# GL3523.net
KiCad netlist of a schematic drawn in Altium Designer
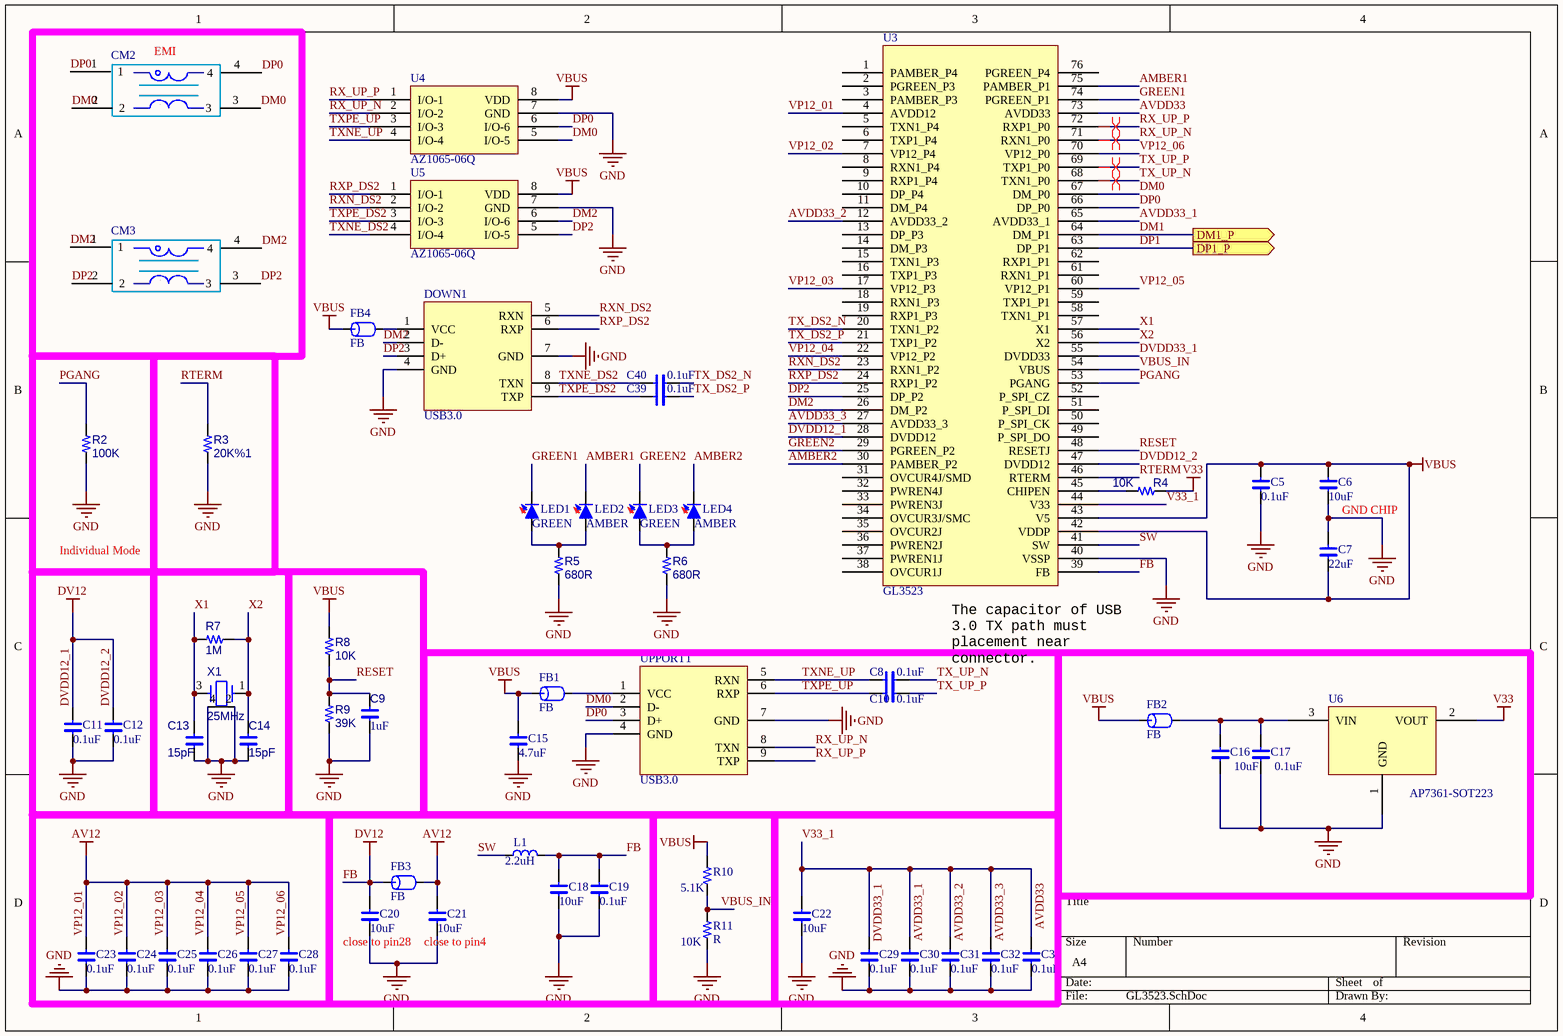
[diagram p0: GL3523.SchDoc]

(export (version "E")
  (design (tool "Eeschema 10.0.6"))
  (components
    (comp (ref "C5")
      (value "C")
      (footprint "0402CAPC1005X06N")
      (fields (field (name "ALTIUM_UNNAMED_1") "0.1uF"))
      (libsource (lib "Schlib_20130601") (part "C"))
    )
    (comp (ref "C6")
      (value "C")
      (footprint "0603CAPC1608X09N")
      (fields (field (name "ALTIUM_UNNAMED_1") "10uF"))
      (libsource (lib "Schlib_20130601") (part "C"))
    )
    (comp (ref "C7")
      (value "C")
      (footprint "0603CAPC1608X09N")
      (fields (field (name "ALTIUM_UNNAMED_1") "22uF"))
      (libsource (lib "Schlib_20130601") (part "C"))
    )
    (comp (ref "C8")
      (value "C")
      (footprint "0402CAPC1005X06N")
      (fields (field (name "ALTIUM_UNNAMED_1") "0.1uF"))
      (libsource (lib "Schlib_20130601") (part "C"))
    )
    (comp (ref "C9")
      (value "15pF")
      (footprint "0402CAPC1005X06N")
      (description "C")
      (fields (field (name "ALTIUM_UNNAMED_1") "1uF"))
      (libsource (lib "Schlib_20130101") (part "C"))
    )
    (comp (ref "C10")
      (value "C")
      (footprint "0402CAPC1005X06N")
      (fields (field (name "ALTIUM_UNNAMED_1") "0.1uF"))
      (libsource (lib "Schlib_20130601") (part "C"))
    )
    (comp (ref "C11")
      (value "C")
      (footprint "0402CAPC1005X06N")
      (fields (field (name "ALTIUM_UNNAMED_1") "0.1uF"))
      (libsource (lib "Schlib_20130601") (part "C"))
    )
    (comp (ref "C12")
      (value "C")
      (footprint "0402CAPC1005X06N")
      (fields (field (name "ALTIUM_UNNAMED_1") "0.1uF"))
      (libsource (lib "Schlib_20130601") (part "C"))
    )
    (comp (ref "C13")
      (value "15pF")
      (footprint "0402CAPC1005X06N")
      (description "C")
      (libsource (lib "Schlib_20130101") (part "C"))
    )
    (comp (ref "C14")
      (value "15pF")
      (footprint "0402CAPC1005X06N")
      (description "C")
      (libsource (lib "Schlib_20130101") (part "C"))
    )
    (comp (ref "C15")
      (value "C")
      (footprint "0603CAPC1608X09N")
      (fields (field (name "ALTIUM_UNNAMED_1") "4.7uF"))
      (libsource (lib "Schlib_20130601") (part "C"))
    )
    (comp (ref "C16")
      (value "C")
      (footprint "0603CAPC1608X09N")
      (fields (field (name "ALTIUM_UNNAMED_1") "10uF"))
      (libsource (lib "Schlib_20130601") (part "C"))
    )
    (comp (ref "C17")
      (value "C")
      (footprint "0402CAPC1005X06N")
      (fields (field (name "ALTIUM_UNNAMED_1") "0.1uF"))
      (libsource (lib "Schlib_20130601") (part "C"))
    )
    (comp (ref "C18")
      (value "C")
      (footprint "0603CAPC1608X09N")
      (fields (field (name "ALTIUM_UNNAMED_1") "10uF"))
      (libsource (lib "Schlib_20130601") (part "C"))
    )
    (comp (ref "C19")
      (value "C")
      (footprint "0402CAPC1005X06N")
      (fields (field (name "ALTIUM_UNNAMED_1") "0.1uF"))
      (libsource (lib "Schlib_20130601") (part "C"))
    )
    (comp (ref "C20")
      (value "C")
      (footprint "0603CAPC1608X09N")
      (fields (field (name "ALTIUM_UNNAMED_1") "10uF"))
      (libsource (lib "Schlib_20130601") (part "C"))
    )
    (comp (ref "C21")
      (value "C")
      (footprint "0603CAPC1608X09N")
      (fields (field (name "ALTIUM_UNNAMED_1") "10uF"))
      (libsource (lib "Schlib_20130601") (part "C"))
    )
    (comp (ref "C22")
      (value "C")
      (footprint "0603CAPC1608X09N")
      (fields (field (name "ALTIUM_UNNAMED_1") "10uF"))
      (libsource (lib "Schlib_20130601") (part "C"))
    )
    (comp (ref "C23")
      (value "C")
      (footprint "0402CAPC1005X06N")
      (fields (field (name "ALTIUM_UNNAMED_1") "0.1uF"))
      (libsource (lib "Schlib_20130601") (part "C"))
    )
    (comp (ref "C24")
      (value "C")
      (footprint "0402CAPC1005X06N")
      (fields (field (name "ALTIUM_UNNAMED_1") "0.1uF"))
      (libsource (lib "Schlib_20130601") (part "C"))
    )
    (comp (ref "C25")
      (value "C")
      (footprint "0402CAPC1005X06N")
      (fields (field (name "ALTIUM_UNNAMED_1") "0.1uF"))
      (libsource (lib "Schlib_20130601") (part "C"))
    )
    (comp (ref "C26")
      (value "C")
      (footprint "0402CAPC1005X06N")
      (fields (field (name "ALTIUM_UNNAMED_1") "0.1uF"))
      (libsource (lib "Schlib_20130601") (part "C"))
    )
    (comp (ref "C27")
      (value "C")
      (footprint "0402CAPC1005X06N")
      (fields (field (name "ALTIUM_UNNAMED_1") "0.1uF"))
      (libsource (lib "Schlib_20130601") (part "C"))
    )
    (comp (ref "C28")
      (value "C")
      (footprint "0402CAPC1005X06N")
      (fields (field (name "ALTIUM_UNNAMED_1") "0.1uF"))
      (libsource (lib "Schlib_20130601") (part "C"))
    )
    (comp (ref "C29")
      (value "C")
      (footprint "0402CAPC1005X06N")
      (fields (field (name "ALTIUM_UNNAMED_1") "0.1uF"))
      (libsource (lib "Schlib_20130601") (part "C"))
    )
    (comp (ref "C30")
      (value "C")
      (footprint "0402CAPC1005X06N")
      (fields (field (name "ALTIUM_UNNAMED_1") "0.1uF"))
      (libsource (lib "Schlib_20130601") (part "C"))
    )
    (comp (ref "C31")
      (value "C")
      (footprint "0402CAPC1005X06N")
      (fields (field (name "ALTIUM_UNNAMED_1") "0.1uF"))
      (libsource (lib "Schlib_20130601") (part "C"))
    )
    (comp (ref "C32")
      (value "C")
      (footprint "0402CAPC1005X06N")
      (fields (field (name "ALTIUM_UNNAMED_1") "0.1uF"))
      (libsource (lib "Schlib_20130601") (part "C"))
    )
    (comp (ref "C33")
      (value "C")
      (footprint "0402CAPC1005X06N")
      (fields (field (name "ALTIUM_UNNAMED_1") "0.1uF"))
      (libsource (lib "Schlib_20130601") (part "C"))
    )
    (comp (ref "C39")
      (value "C")
      (footprint "0402CAPC1005X06N")
      (fields (field (name "ALTIUM_UNNAMED_1") "0.1uF"))
      (libsource (lib "Schlib_20130601") (part "C"))
    )
    (comp (ref "C40")
      (value "C")
      (footprint "0402CAPC1005X06N")
      (fields (field (name "ALTIUM_UNNAMED_1") "0.1uF"))
      (libsource (lib "Schlib_20130601") (part "C"))
    )
    (comp (ref "CM2")
      (value "CM")
      (footprint "SMD_4P")
      (description "USB Comon Choke")
      (libsource (lib "Schlib_20130601") (part "CM"))
    )
    (comp (ref "CM3")
      (value "CM")
      (footprint "SMD_4P")
      (description "USB Comon Choke")
      (libsource (lib "Schlib_20130601") (part "CM"))
    )
    (comp (ref "DOWN1")
      (value "USB3.0")
      (footprint "USB3.0-A-Pin")
      (libsource (lib "Schlib_20130601") (part "USB3.0"))
    )
    (comp (ref "FB1") (value "FB") (footprint "0805FB") (libsource (lib "Schlib_20130601") (part "FB")))
    (comp (ref "FB2") (value "FB") (footprint "0805FB") (libsource (lib "Schlib_20130601") (part "FB")))
    (comp (ref "FB3") (value "FB") (footprint "0805FB") (libsource (lib "Schlib_20130601") (part "FB")))
    (comp (ref "FB4") (value "FB") (footprint "0805FB") (libsource (lib "Schlib_20130601") (part "FB")))
    (comp (ref "L1")
      (value "L")
      (footprint "0805FB")
      (fields (field (name "ALTIUM_UNNAMED_1") "2.2uH"))
      (libsource (lib "Schlib_20130601") (part "L"))
    )
    (comp (ref "LED1")
      (value "GREEN")
      (footprint "0603LEDC1608X04N")
      (description "Chip LED")
      (fields (field (name "PUBLISHER") "ChenTao"))
      (libsource (lib "THTF_SCHLIB_V1P0_20130724") (part "LED"))
    )
    (comp (ref "LED2")
      (value "AMBER")
      (footprint "0603LEDC1608X04N")
      (description "Chip LED")
      (fields (field (name "PUBLISHER") "ChenTao"))
      (libsource (lib "THTF_SCHLIB_V1P0_20130724") (part "LED"))
    )
    (comp (ref "LED3")
      (value "GREEN")
      (footprint "0603LEDC1608X04N")
      (description "Chip LED")
      (fields (field (name "PUBLISHER") "ChenTao"))
      (libsource (lib "THTF_SCHLIB_V1P0_20130724") (part "LED"))
    )
    (comp (ref "LED4")
      (value "AMBER")
      (footprint "0603LEDC1608X04N")
      (description "Chip LED")
      (fields (field (name "PUBLISHER") "ChenTao"))
      (libsource (lib "THTF_SCHLIB_V1P0_20130724") (part "LED"))
    )
    (comp (ref "R2")
      (value "100K")
      (footprint "0402RESC1005X04N")
      (description "R")
      (libsource (lib "Schlib_20130101") (part "R"))
    )
    (comp (ref "R3")
      (value "20K%1")
      (footprint "0402RESC1005X04N")
      (description "R")
      (libsource (lib "Schlib_20130101") (part "R"))
    )
    (comp (ref "R4")
      (value "10K")
      (footprint "0402RESC1005X04N")
      (description "R")
      (libsource (lib "Schlib_20130101") (part "R"))
    )
    (comp (ref "R5")
      (value "680R")
      (footprint "0402RESC1005X04N")
      (description "R")
      (libsource (lib "Schlib_20130101") (part "R"))
    )
    (comp (ref "R6")
      (value "680R")
      (footprint "0402RESC1005X04N")
      (description "R")
      (libsource (lib "Schlib_20130101") (part "R"))
    )
    (comp (ref "R7")
      (value "1M")
      (footprint "0402RESC1005X04N")
      (description "R")
      (libsource (lib "Schlib_20130101") (part "R"))
    )
    (comp (ref "R8")
      (value "10K")
      (footprint "0402RESC1005X04N")
      (description "R")
      (libsource (lib "Schlib_20130101") (part "R"))
    )
    (comp (ref "R9")
      (value "39K")
      (footprint "0402RESC1005X04N")
      (description "R")
      (libsource (lib "Schlib_20130101") (part "R"))
    )
    (comp (ref "R10")
      (value "R")
      (footprint "0603R")
      (fields (field (name "ALTIUM_UNNAMED_1") "5.1K"))
      (libsource (lib "Schlib_20130601") (part "R"))
    )
    (comp (ref "R11")
      (value "R")
      (footprint "0603R")
      (fields (field (name "ALTIUM_UNNAMED_1") "10K"))
      (libsource (lib "Schlib_20130601") (part "R"))
    )
    (comp (ref "U3")
      (value "GL3523")
      (footprint "QFN-76")
      (libsource (lib "Schlib_20130601") (part "GL3523"))
    )
    (comp (ref "U4")
      (value "AZ1065-06Q")
      (footprint "MSOP-8")
      (libsource (lib "Schlib_20130601") (part "AZ1065-06Q"))
    )
    (comp (ref "U5")
      (value "AZ1065-06Q")
      (footprint "MSOP-8")
      (libsource (lib "Schlib_20130601") (part "AZ1065-06Q"))
    )
    (comp (ref "U6")
      (value "AP7361-SOT223")
      (footprint "SOT230P700X180-4N")
      (libsource (lib "Schlib_20130601") (part "AMS1117-3.3"))
    )
    (comp (ref "UPPORT1")
      (value "USB3.0")
      (footprint "USB3.0-G")
      (libsource (lib "Schlib_20130601") (part "USB3.0"))
    )
    (comp (ref "X1")
      (value "25MHz")
      (footprint "CPX-32")
      (libsource (lib "Schlib_20110825") (part "CRYSTAL-4"))
    )
  )
  (nets
    (net (code "1") (name "/AMBER1") (class "Default")
      (node (ref "LED2") (pin "K") (pintype "passive"))
      (node (ref "U3") (pin "75") (pinfunction "PAMBER_P1_75") (pintype "passive"))
    )
    (net (code "2") (name "/AMBER2") (class "Default")
      (node (ref "LED4") (pin "K") (pintype "passive"))
      (node (ref "U3") (pin "30") (pinfunction "PAMBER_P2_30") (pintype "passive"))
    )
    (net (code "3") (name "/AVDD33") (class "Default")
      (node (ref "C22") (pin "2") (pintype "passive"))
      (node (ref "C29") (pin "2") (pintype "passive"))
      (node (ref "C30") (pin "2") (pintype "passive"))
      (node (ref "C31") (pin "2") (pintype "passive"))
      (node (ref "C32") (pin "2") (pintype "passive"))
      (node (ref "C33") (pin "2") (pintype "passive"))
      (node (ref "U3") (pin "12") (pinfunction "AVDD33_2_12") (pintype "passive"))
      (node (ref "U3") (pin "27") (pinfunction "AVDD33_3_27") (pintype "passive"))
      (node (ref "U3") (pin "44") (pinfunction "V33_44") (pintype "passive"))
      (node (ref "U3") (pin "55") (pinfunction "DVDD33_55") (pintype "passive"))
      (node (ref "U3") (pin "65") (pinfunction "AVDD33_1_65") (pintype "passive"))
      (node (ref "U3") (pin "73") (pinfunction "AVDD33_73") (pintype "passive"))
    )
    (net (code "4") (name "/DM0") (class "Default")
      (node (ref "CM2") (pin "2") (pinfunction "2_2") (pintype "passive"))
      (node (ref "CM2") (pin "3") (pinfunction "3_3") (pintype "passive"))
      (node (ref "U3") (pin "67") (pinfunction "DM_P0_67") (pintype "passive"))
      (node (ref "U4") (pin "5") (pinfunction "I/O-5_5") (pintype "passive"))
      (node (ref "UPPORT1") (pin "2") (pinfunction "D-_2") (pintype "passive"))
    )
    (net (code "5") (name "/DM1") (class "Default")
      (node (ref "U3") (pin "64") (pinfunction "DM_P1_64") (pintype "passive"))
    )
    (net (code "6") (name "/DM2") (class "Default")
      (node (ref "CM3") (pin "1") (pinfunction "1_1") (pintype "passive"))
      (node (ref "CM3") (pin "4") (pinfunction "4_4") (pintype "passive"))
      (node (ref "DOWN1") (pin "2") (pinfunction "D-_2") (pintype "passive"))
      (node (ref "U3") (pin "26") (pinfunction "DM_P2_26") (pintype "passive"))
      (node (ref "U5") (pin "6") (pinfunction "I/O-6_6") (pintype "passive"))
    )
    (net (code "7") (name "/DP0") (class "Default")
      (node (ref "CM2") (pin "1") (pinfunction "1_1") (pintype "passive"))
      (node (ref "CM2") (pin "4") (pinfunction "4_4") (pintype "passive"))
      (node (ref "U3") (pin "66") (pinfunction "DP_P0_66") (pintype "passive"))
      (node (ref "U4") (pin "6") (pinfunction "I/O-6_6") (pintype "passive"))
      (node (ref "UPPORT1") (pin "3") (pinfunction "D+_3") (pintype "passive"))
    )
    (net (code "8") (name "/DP1") (class "Default")
      (node (ref "U3") (pin "63") (pinfunction "DP_P1_63") (pintype "passive"))
    )
    (net (code "9") (name "/DP2") (class "Default")
      (node (ref "CM3") (pin "2") (pinfunction "2_2") (pintype "passive"))
      (node (ref "CM3") (pin "3") (pinfunction "3_3") (pintype "passive"))
      (node (ref "DOWN1") (pin "3") (pinfunction "D+_3") (pintype "passive"))
      (node (ref "U3") (pin "25") (pinfunction "DP_P2_25") (pintype "passive"))
      (node (ref "U5") (pin "5") (pinfunction "I/O-5_5") (pintype "passive"))
    )
    (net (code "10") (name "/GREEN1") (class "Default")
      (node (ref "LED1") (pin "K") (pintype "passive"))
      (node (ref "U3") (pin "74") (pinfunction "PGREEN_P1_74") (pintype "passive"))
    )
    (net (code "11") (name "/GREEN2") (class "Default")
      (node (ref "LED3") (pin "K") (pintype "passive"))
      (node (ref "U3") (pin "29") (pinfunction "PGREEN_P2_29") (pintype "passive"))
    )
    (net (code "12") (name "/PGANG") (class "Default")
      (node (ref "R2") (pin "1") (pintype "passive"))
      (node (ref "U3") (pin "53") (pinfunction "PGANG_53") (pintype "passive"))
    )
    (net (code "13") (name "/RESET") (class "Default")
      (node (ref "C9") (pin "1") (pintype "passive"))
      (node (ref "R8") (pin "2") (pintype "passive"))
      (node (ref "R9") (pin "1") (pintype "passive"))
      (node (ref "U3") (pin "48") (pinfunction "RESETJ_48") (pintype "passive"))
    )
    (net (code "14") (name "/RTERM") (class "Default")
      (node (ref "R3") (pin "1") (pintype "passive"))
      (node (ref "U3") (pin "46") (pinfunction "RTERM_46") (pintype "passive"))
    )
    (net (code "15") (name "/RXN_DS2") (class "Default")
      (node (ref "DOWN1") (pin "5") (pinfunction "RXN_5") (pintype "passive"))
      (node (ref "U3") (pin "23") (pinfunction "RXN1_P2_23") (pintype "passive"))
      (node (ref "U5") (pin "2") (pinfunction "I/O-2_2") (pintype "passive"))
    )
    (net (code "16") (name "/RXP_DS2") (class "Default")
      (node (ref "DOWN1") (pin "6") (pinfunction "RXP_6") (pintype "passive"))
      (node (ref "U3") (pin "24") (pinfunction "RXP1_P2_24") (pintype "passive"))
      (node (ref "U5") (pin "1") (pinfunction "I/O-1_1") (pintype "passive"))
    )
    (net (code "17") (name "/RX_UP_N") (class "Default")
      (node (ref "U3") (pin "71") (pinfunction "RXN1_P0_71") (pintype "passive"))
      (node (ref "U4") (pin "2") (pinfunction "I/O-2_2") (pintype "passive"))
      (node (ref "UPPORT1") (pin "8") (pinfunction "TXN_8") (pintype "passive"))
    )
    (net (code "18") (name "/RX_UP_P") (class "Default")
      (node (ref "U3") (pin "72") (pinfunction "RXP1_P0_72") (pintype "passive"))
      (node (ref "U4") (pin "1") (pinfunction "I/O-1_1") (pintype "passive"))
      (node (ref "UPPORT1") (pin "9") (pinfunction "TXP_9") (pintype "passive"))
    )
    (net (code "19") (name "/SW") (class "Default")
      (node (ref "L1") (pin "1") (pintype "passive"))
      (node (ref "U3") (pin "41") (pinfunction "SW_41") (pintype "passive"))
    )
    (net (code "20") (name "/TXNE_DS2") (class "Default")
      (node (ref "C40") (pin "2") (pintype "passive"))
      (node (ref "DOWN1") (pin "8") (pinfunction "TXN_8") (pintype "passive"))
      (node (ref "U5") (pin "4") (pinfunction "I/O-4_4") (pintype "passive"))
    )
    (net (code "21") (name "/TXNE_UP") (class "Default")
      (node (ref "C8") (pin "2") (pintype "passive"))
      (node (ref "U4") (pin "4") (pinfunction "I/O-4_4") (pintype "passive"))
      (node (ref "UPPORT1") (pin "5") (pinfunction "RXN_5") (pintype "passive"))
    )
    (net (code "22") (name "/TXPE_DS2") (class "Default")
      (node (ref "C39") (pin "2") (pintype "passive"))
      (node (ref "DOWN1") (pin "9") (pinfunction "TXP_9") (pintype "passive"))
      (node (ref "U5") (pin "3") (pinfunction "I/O-3_3") (pintype "passive"))
    )
    (net (code "23") (name "/TXPE_UP") (class "Default")
      (node (ref "C10") (pin "2") (pintype "passive"))
      (node (ref "U4") (pin "3") (pinfunction "I/O-3_3") (pintype "passive"))
      (node (ref "UPPORT1") (pin "6") (pinfunction "RXP_6") (pintype "passive"))
    )
    (net (code "24") (name "/TX_DS2_N") (class "Default")
      (node (ref "C40") (pin "1") (pintype "passive"))
      (node (ref "U3") (pin "20") (pinfunction "TXN1_P2_20") (pintype "passive"))
    )
    (net (code "25") (name "/TX_DS2_P") (class "Default")
      (node (ref "C39") (pin "1") (pintype "passive"))
      (node (ref "U3") (pin "21") (pinfunction "TXP1_P2_21") (pintype "passive"))
    )
    (net (code "26") (name "/TX_UP_N") (class "Default")
      (node (ref "C8") (pin "1") (pintype "passive"))
      (node (ref "U3") (pin "68") (pinfunction "TXN1_P0_68") (pintype "passive"))
    )
    (net (code "27") (name "/TX_UP_P") (class "Default")
      (node (ref "C10") (pin "1") (pintype "passive"))
      (node (ref "U3") (pin "69") (pinfunction "TXP1_P0_69") (pintype "passive"))
    )
    (net (code "28") (name "/VBUS_IN") (class "Default")
      (node (ref "R10") (pin "1") (pintype "passive"))
      (node (ref "R11") (pin "2") (pintype "passive"))
      (node (ref "U3") (pin "54") (pinfunction "VBUS_54") (pintype "passive"))
    )
    (net (code "29") (name "/X1") (class "Default")
      (node (ref "C13") (pin "2") (pintype "passive"))
      (node (ref "R7") (pin "2") (pintype "passive"))
      (node (ref "U3") (pin "57") (pinfunction "X1_57") (pintype "passive"))
      (node (ref "X1") (pin "3") (pinfunction "X2_3") (pintype "passive"))
    )
    (net (code "30") (name "/X2") (class "Default")
      (node (ref "C14") (pin "1") (pintype "passive"))
      (node (ref "R7") (pin "1") (pintype "passive"))
      (node (ref "U3") (pin "56") (pinfunction "X2_56") (pintype "passive"))
      (node (ref "X1") (pin "1") (pinfunction "X1_1") (pintype "passive"))
    )
    (net (code "31") (name "AV12") (class "Default")
      (node (ref "C21") (pin "2") (pintype "passive"))
      (node (ref "C23") (pin "2") (pintype "passive"))
      (node (ref "C24") (pin "2") (pintype "passive"))
      (node (ref "C25") (pin "2") (pintype "passive"))
      (node (ref "C26") (pin "2") (pintype "passive"))
      (node (ref "C27") (pin "2") (pintype "passive"))
      (node (ref "C28") (pin "2") (pintype "passive"))
      (node (ref "FB3") (pin "2") (pintype "passive"))
      (node (ref "U3") (pin "17") (pinfunction "VP12_P3_17") (pintype "passive"))
      (node (ref "U3") (pin "22") (pinfunction "VP12_P2_22") (pintype "passive"))
      (node (ref "U3") (pin "4") (pinfunction "AVDD12_4") (pintype "passive"))
      (node (ref "U3") (pin "60") (pinfunction "VP12_P1_60") (pintype "passive"))
      (node (ref "U3") (pin "7") (pinfunction "VP12_P4_7") (pintype "passive"))
      (node (ref "U3") (pin "70") (pinfunction "VP12_P0_70") (pintype "passive"))
    )
    (net (code "32") (name "DV12") (class "Default")
      (node (ref "C11") (pin "2") (pintype "passive"))
      (node (ref "C12") (pin "2") (pintype "passive"))
      (node (ref "C18") (pin "2") (pintype "passive"))
      (node (ref "C19") (pin "2") (pintype "passive"))
      (node (ref "C20") (pin "2") (pintype "passive"))
      (node (ref "FB3") (pin "1") (pintype "passive"))
      (node (ref "L1") (pin "2") (pintype "passive"))
      (node (ref "U3") (pin "28") (pinfunction "DVDD12_28") (pintype "passive"))
      (node (ref "U3") (pin "39") (pinfunction "FB_39") (pintype "passive"))
      (node (ref "U3") (pin "47") (pinfunction "DVDD12_47") (pintype "passive"))
    )
    (net (code "33") (name "GND") (class "Default")
      (node (ref "C11") (pin "1") (pintype "passive"))
      (node (ref "C12") (pin "1") (pintype "passive"))
      (node (ref "C13") (pin "1") (pintype "passive"))
      (node (ref "C14") (pin "2") (pintype "passive"))
      (node (ref "C15") (pin "1") (pintype "passive"))
      (node (ref "C16") (pin "1") (pintype "passive"))
      (node (ref "C17") (pin "1") (pintype "passive"))
      (node (ref "C18") (pin "1") (pintype "passive"))
      (node (ref "C19") (pin "1") (pintype "passive"))
      (node (ref "C20") (pin "1") (pintype "passive"))
      (node (ref "C21") (pin "1") (pintype "passive"))
      (node (ref "C22") (pin "1") (pintype "passive"))
      (node (ref "C23") (pin "1") (pintype "passive"))
      (node (ref "C24") (pin "1") (pintype "passive"))
      (node (ref "C25") (pin "1") (pintype "passive"))
      (node (ref "C26") (pin "1") (pintype "passive"))
      (node (ref "C27") (pin "1") (pintype "passive"))
      (node (ref "C28") (pin "1") (pintype "passive"))
      (node (ref "C29") (pin "1") (pintype "passive"))
      (node (ref "C30") (pin "1") (pintype "passive"))
      (node (ref "C31") (pin "1") (pintype "passive"))
      (node (ref "C32") (pin "1") (pintype "passive"))
      (node (ref "C33") (pin "1") (pintype "passive"))
      (node (ref "C5") (pin "1") (pintype "passive"))
      (node (ref "C6") (pin "1") (pintype "passive"))
      (node (ref "C7") (pin "2") (pintype "passive"))
      (node (ref "C9") (pin "2") (pintype "passive"))
      (node (ref "DOWN1") (pin "4") (pinfunction "GND_4") (pintype "passive"))
      (node (ref "DOWN1") (pin "7") (pinfunction "GND_7") (pintype "passive"))
      (node (ref "R11") (pin "1") (pintype "passive"))
      (node (ref "R2") (pin "2") (pintype "passive"))
      (node (ref "R3") (pin "2") (pintype "passive"))
      (node (ref "R5") (pin "2") (pintype "passive"))
      (node (ref "R6") (pin "2") (pintype "passive"))
      (node (ref "R9") (pin "2") (pintype "passive"))
      (node (ref "U3") (pin "40") (pinfunction "VSSP_40") (pintype "passive"))
      (node (ref "U4") (pin "7") (pinfunction "GND_7") (pintype "passive"))
      (node (ref "U5") (pin "7") (pinfunction "GND_7") (pintype "passive"))
      (node (ref "U6") (pin "1") (pinfunction "GND_1") (pintype "passive"))
      (node (ref "UPPORT1") (pin "4") (pinfunction "GND_4") (pintype "passive"))
      (node (ref "UPPORT1") (pin "7") (pinfunction "GND_7") (pintype "passive"))
      (node (ref "X1") (pin "2") (pinfunction "GND_2") (pintype "passive"))
      (node (ref "X1") (pin "4") (pinfunction "GND_4") (pintype "passive"))
    )
    (net (code "34") (name "Net-(DOWN1-VCC)") (class "Default")
      (node (ref "DOWN1") (pin "1") (pinfunction "VCC_1") (pintype "passive"))
      (node (ref "FB4") (pin "2") (pintype "passive"))
    )
    (net (code "35") (name "Net-(LED1-PadA)") (class "Default")
      (node (ref "LED1") (pin "A") (pintype "passive"))
      (node (ref "LED2") (pin "A") (pintype "passive"))
      (node (ref "R5") (pin "1") (pintype "passive"))
    )
    (net (code "36") (name "Net-(LED3-PadA)") (class "Default")
      (node (ref "LED3") (pin "A") (pintype "passive"))
      (node (ref "LED4") (pin "A") (pintype "passive"))
      (node (ref "R6") (pin "1") (pintype "passive"))
    )
    (net (code "37") (name "Net-(U3-CHIPEN)") (class "Default")
      (node (ref "R4") (pin "2") (pintype "passive"))
      (node (ref "U3") (pin "45") (pinfunction "CHIPEN_45") (pintype "passive"))
    )
    (net (code "38") (name "Net-(U6-VIN)") (class "Default")
      (node (ref "C16") (pin "2") (pintype "passive"))
      (node (ref "C17") (pin "2") (pintype "passive"))
      (node (ref "FB2") (pin "2") (pintype "passive"))
      (node (ref "U6") (pin "3") (pinfunction "VIN_3") (pintype "passive"))
    )
    (net (code "39") (name "Net-(UPPORT1-VCC)") (class "Default")
      (node (ref "FB1") (pin "2") (pintype "passive"))
      (node (ref "UPPORT1") (pin "1") (pinfunction "VCC_1") (pintype "passive"))
    )
    (net (code "40") (name "V33") (class "Default")
      (node (ref "R4") (pin "1") (pintype "passive"))
      (node (ref "U6") (pin "2") (pinfunction "VOUT_2") (pintype "passive"))
    )
    (net (code "41") (name "VBUS") (class "Default")
      (node (ref "C15") (pin "2") (pintype "passive"))
      (node (ref "C5") (pin "2") (pintype "passive"))
      (node (ref "C6") (pin "2") (pintype "passive"))
      (node (ref "C7") (pin "1") (pintype "passive"))
      (node (ref "FB1") (pin "1") (pintype "passive"))
      (node (ref "FB2") (pin "1") (pintype "passive"))
      (node (ref "FB4") (pin "1") (pintype "passive"))
      (node (ref "R10") (pin "2") (pintype "passive"))
      (node (ref "R8") (pin "1") (pintype "passive"))
      (node (ref "U3") (pin "42") (pinfunction "VDDP_42") (pintype "passive"))
      (node (ref "U3") (pin "43") (pinfunction "V5_43") (pintype "passive"))
      (node (ref "U4") (pin "8") (pinfunction "VDD_8") (pintype "passive"))
      (node (ref "U5") (pin "8") (pinfunction "VDD_8") (pintype "passive"))
    )
    (net (code "42") (name "unconnected-(U3-DM_P3-Pad14)") (class "Default")
      (node (ref "U3") (pin "14") (pinfunction "DM_P3_14") (pintype "passive"))
    )
    (net (code "43") (name "unconnected-(U3-DM_P4-Pad11)") (class "Default")
      (node (ref "U3") (pin "11") (pinfunction "DM_P4_11") (pintype "passive"))
    )
    (net (code "44") (name "unconnected-(U3-DP_P3-Pad13)") (class "Default")
      (node (ref "U3") (pin "13") (pinfunction "DP_P3_13") (pintype "passive"))
    )
    (net (code "45") (name "unconnected-(U3-DP_P4-Pad10)") (class "Default")
      (node (ref "U3") (pin "10") (pinfunction "DP_P4_10") (pintype "passive"))
    )
    (net (code "46") (name "unconnected-(U3-OVCUR1J-Pad38)") (class "Default")
      (node (ref "U3") (pin "38") (pinfunction "OVCUR1J_38") (pintype "passive"))
    )
    (net (code "47") (name "unconnected-(U3-OVCUR2J-Pad35)") (class "Default")
      (node (ref "U3") (pin "35") (pinfunction "OVCUR2J_35") (pintype "passive"))
    )
    (net (code "48") (name "unconnected-(U3-OVCUR3J{slash}SMC-Pad34)") (class "Default")
      (node (ref "U3") (pin "34") (pinfunction "OVCUR3J/SMC_34") (pintype "passive"))
    )
    (net (code "49") (name "unconnected-(U3-OVCUR4J{slash}SMD-Pad31)") (class "Default")
      (node (ref "U3") (pin "31") (pinfunction "OVCUR4J/SMD_31") (pintype "passive"))
    )
    (net (code "50") (name "unconnected-(U3-PAMBER_P3-Pad3)") (class "Default")
      (node (ref "U3") (pin "3") (pinfunction "PAMBER_P3_3") (pintype "passive"))
    )
    (net (code "51") (name "unconnected-(U3-PAMBER_P4-Pad1)") (class "Default")
      (node (ref "U3") (pin "1") (pinfunction "PAMBER_P4_1") (pintype "passive"))
    )
    (net (code "52") (name "unconnected-(U3-PGREEN_P3-Pad2)") (class "Default")
      (node (ref "U3") (pin "2") (pinfunction "PGREEN_P3_2") (pintype "passive"))
    )
    (net (code "53") (name "unconnected-(U3-PGREEN_P4-Pad76)") (class "Default")
      (node (ref "U3") (pin "76") (pinfunction "PGREEN_P4_76") (pintype "passive"))
    )
    (net (code "54") (name "unconnected-(U3-PWREN1J-Pad37)") (class "Default")
      (node (ref "U3") (pin "37") (pinfunction "PWREN1J_37") (pintype "passive"))
    )
    (net (code "55") (name "unconnected-(U3-PWREN2J-Pad36)") (class "Default")
      (node (ref "U3") (pin "36") (pinfunction "PWREN2J_36") (pintype "passive"))
    )
    (net (code "56") (name "unconnected-(U3-PWREN3J-Pad33)") (class "Default")
      (node (ref "U3") (pin "33") (pinfunction "PWREN3J_33") (pintype "passive"))
    )
    (net (code "57") (name "unconnected-(U3-PWREN4J-Pad32)") (class "Default")
      (node (ref "U3") (pin "32") (pinfunction "PWREN4J_32") (pintype "passive"))
    )
    (net (code "58") (name "unconnected-(U3-P_SPI_CK-Pad50)") (class "Default")
      (node (ref "U3") (pin "50") (pinfunction "P_SPI_CK_50") (pintype "passive"))
    )
    (net (code "59") (name "unconnected-(U3-P_SPI_CZ-Pad52)") (class "Default")
      (node (ref "U3") (pin "52") (pinfunction "P_SPI_CZ_52") (pintype "passive"))
    )
    (net (code "60") (name "unconnected-(U3-P_SPI_DI-Pad51)") (class "Default")
      (node (ref "U3") (pin "51") (pinfunction "P_SPI_DI_51") (pintype "passive"))
    )
    (net (code "61") (name "unconnected-(U3-P_SPI_DO-Pad49)") (class "Default")
      (node (ref "U3") (pin "49") (pinfunction "P_SPI_DO_49") (pintype "passive"))
    )
    (net (code "62") (name "unconnected-(U3-RXN1_P1-Pad61)") (class "Default")
      (node (ref "U3") (pin "61") (pinfunction "RXN1_P1_61") (pintype "passive"))
    )
    (net (code "63") (name "unconnected-(U3-RXN1_P3-Pad18)") (class "Default")
      (node (ref "U3") (pin "18") (pinfunction "RXN1_P3_18") (pintype "passive"))
    )
    (net (code "64") (name "unconnected-(U3-RXN1_P4-Pad8)") (class "Default")
      (node (ref "U3") (pin "8") (pinfunction "RXN1_P4_8") (pintype "passive"))
    )
    (net (code "65") (name "unconnected-(U3-RXP1_P1-Pad62)") (class "Default")
      (node (ref "U3") (pin "62") (pinfunction "RXP1_P1_62") (pintype "passive"))
    )
    (net (code "66") (name "unconnected-(U3-RXP1_P3-Pad19)") (class "Default")
      (node (ref "U3") (pin "19") (pinfunction "RXP1_P3_19") (pintype "passive"))
    )
    (net (code "67") (name "unconnected-(U3-RXP1_P4-Pad9)") (class "Default")
      (node (ref "U3") (pin "9") (pinfunction "RXP1_P4_9") (pintype "passive"))
    )
    (net (code "68") (name "unconnected-(U3-TXN1_P1-Pad58)") (class "Default")
      (node (ref "U3") (pin "58") (pinfunction "TXN1_P1_58") (pintype "passive"))
    )
    (net (code "69") (name "unconnected-(U3-TXN1_P3-Pad15)") (class "Default")
      (node (ref "U3") (pin "15") (pinfunction "TXN1_P3_15") (pintype "passive"))
    )
    (net (code "70") (name "unconnected-(U3-TXN1_P4-Pad5)") (class "Default")
      (node (ref "U3") (pin "5") (pinfunction "TXN1_P4_5") (pintype "passive"))
    )
    (net (code "71") (name "unconnected-(U3-TXP1_P1-Pad59)") (class "Default")
      (node (ref "U3") (pin "59") (pinfunction "TXP1_P1_59") (pintype "passive"))
    )
    (net (code "72") (name "unconnected-(U3-TXP1_P3-Pad16)") (class "Default")
      (node (ref "U3") (pin "16") (pinfunction "TXP1_P3_16") (pintype "passive"))
    )
    (net (code "73") (name "unconnected-(U3-TXP1_P4-Pad6)") (class "Default")
      (node (ref "U3") (pin "6") (pinfunction "TXP1_P4_6") (pintype "passive"))
    )
  )
)
